# CAN.net
KiCad netlist of a schematic drawn in Altium Designer
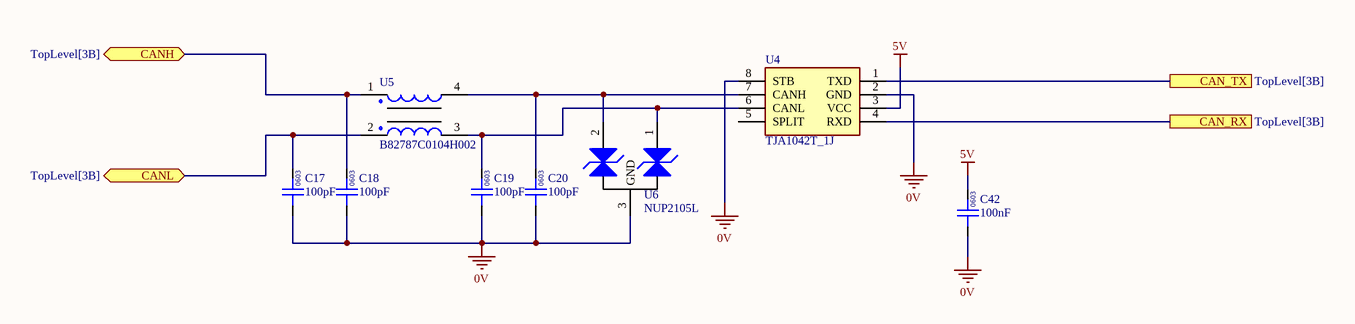
[diagram p0: CAN.SchDoc]

(export (version "E")
  (design (tool "Eeschema 10.0.6"))
  (components
    (comp (ref "C17")
      (value "100pF")
      (footprint "0603")
      (fields
        (field (name "PART NUMBER") "GRM1885C1H101JA01D")
        (field (name "MANUFACTURER") "Murata Electronics")
        (field (name "TOLERANCE") "±5%")
      )
      (libsource (lib "ts_standard_library") (part "Capacitor 0603"))
    )
    (comp (ref "C18")
      (value "100pF")
      (footprint "0603")
      (fields
        (field (name "PART NUMBER") "GRM1885C1H101JA01D")
        (field (name "MANUFACTURER") "Murata Electronics")
        (field (name "TOLERANCE") "±5%")
      )
      (libsource (lib "ts_standard_library") (part "Capacitor 0603"))
    )
    (comp (ref "C19")
      (value "100pF")
      (footprint "0603")
      (fields
        (field (name "PART NUMBER") "GRM1885C1H101JA01D")
        (field (name "MANUFACTURER") "Murata Electronics")
        (field (name "TOLERANCE") "±5%")
      )
      (libsource (lib "ts_standard_library") (part "Capacitor 0603"))
    )
    (comp (ref "C20")
      (value "100pF")
      (footprint "0603")
      (fields
        (field (name "PART NUMBER") "GRM1885C1H101JA01D")
        (field (name "MANUFACTURER") "Murata Electronics")
        (field (name "TOLERANCE") "±5%")
      )
      (libsource (lib "ts_standard_library") (part "Capacitor 0603"))
    )
    (comp (ref "C42")
      (value "100nF")
      (footprint "0603")
      (fields
        (field (name "PART NUMBER") "GCM188L81H104KA57D")
        (field (name "MANUFACTURER") "muRata")
        (field (name "TOLERANCE") "±10%")
      )
      (libsource (lib "ts_standard_library") (part "Capacitor 0603"))
    )
    (comp (ref "U4")
      (value "TJA1042T_1J")
      (footprint "SamacSys:SOIC127P600X175-8N")
      (description "Integrated Circuit")
      (fields
        (field (name "MANUFACTURER_PART_NUMBER") "TJA1042T/1J")
        (field (name "MOUSER PART NUMBER") "771-TJA1042T/1J")
      )
      (libsource (lib "*") (part "TJA1042T_1J"))
    )
    (comp (ref "U5")
      (value "B82787C0104H002")
      (footprint "TDK 4-PC Pad")
      (fields
        (field (name "MANUFACTURER") "EPCOS (TDK)")
        (field (name "DIGIKEY PART NUMBER") "495-4598-1-ND")
      )
      (libsource (lib "ts_standard_library") (part "B82787C0104H002"))
    )
    (comp (ref "U6")
      (value "NUP2105L")
      (footprint "ON SOT-23")
      (description "Dual Line CAN Bus Protector")
      (fields
        (field (name "MANUFACTURER") "ON Semiconductor")
        (field (name "DIGIKEY PART NUMBER") "NUP2105LT1GOSCT-ND")
      )
      (libsource (lib "ts_standard_library") (part "NUP2105L"))
    )
  )
  (nets
    (net (code "1") (name "/CANH") (class "Default")
      (node (ref "C18") (pin "2") (pinfunction "2_2") (pintype "passive"))
      (node (ref "U5") (pin "1") (pinfunction "1_1") (pintype "passive"))
    )
    (net (code "2") (name "/CANL") (class "Default")
      (node (ref "C17") (pin "2") (pinfunction "2_2") (pintype "passive"))
      (node (ref "U5") (pin "2") (pinfunction "2_2") (pintype "passive"))
    )
    (net (code "3") (name "/CAN_RX") (class "Default")
      (node (ref "U4") (pin "4") (pinfunction "RXD_4") (pintype "passive"))
    )
    (net (code "4") (name "/CAN_TX") (class "Default")
      (node (ref "U4") (pin "1") (pinfunction "TXD_1") (pintype "passive"))
    )
    (net (code "5") (name "0V") (class "Default")
      (node (ref "C17") (pin "1") (pinfunction "1_1") (pintype "passive"))
      (node (ref "C18") (pin "1") (pinfunction "1_1") (pintype "passive"))
      (node (ref "C19") (pin "1") (pinfunction "1_1") (pintype "passive"))
      (node (ref "C20") (pin "1") (pinfunction "1_1") (pintype "passive"))
      (node (ref "C42") (pin "1") (pinfunction "1_1") (pintype "passive"))
      (node (ref "U4") (pin "2") (pinfunction "GND_2") (pintype "passive"))
      (node (ref "U4") (pin "8") (pinfunction "STB_8") (pintype "passive"))
      (node (ref "U6") (pin "3") (pinfunction "GND_3") (pintype "passive"))
    )
    (net (code "6") (name "5V") (class "Default")
      (node (ref "C42") (pin "2") (pinfunction "2_2") (pintype "passive"))
      (node (ref "U4") (pin "3") (pinfunction "VCC_3") (pintype "passive"))
    )
    (net (code "7") (name "Net-(U4-CANH)") (class "Default")
      (node (ref "C20") (pin "2") (pinfunction "2_2") (pintype "passive"))
      (node (ref "U4") (pin "7") (pinfunction "CANH_7") (pintype "passive"))
      (node (ref "U5") (pin "4") (pinfunction "4_4") (pintype "passive"))
      (node (ref "U6") (pin "2") (pinfunction "CAN_L_2") (pintype "passive"))
    )
    (net (code "8") (name "Net-(U4-CANL)") (class "Default")
      (node (ref "C19") (pin "2") (pinfunction "2_2") (pintype "passive"))
      (node (ref "U4") (pin "6") (pinfunction "CANL_6") (pintype "passive"))
      (node (ref "U5") (pin "3") (pinfunction "3_3") (pintype "passive"))
      (node (ref "U6") (pin "1") (pinfunction "CAN_H_1") (pintype "passive"))
    )
    (net (code "9") (name "unconnected-(U4-SPLIT-Pad5)") (class "Default")
      (node (ref "U4") (pin "5") (pinfunction "SPLIT_5") (pintype "passive"))
    )
  )
)
